# general_Interface.net
KiCad netlist of a schematic drawn in Altium Designer
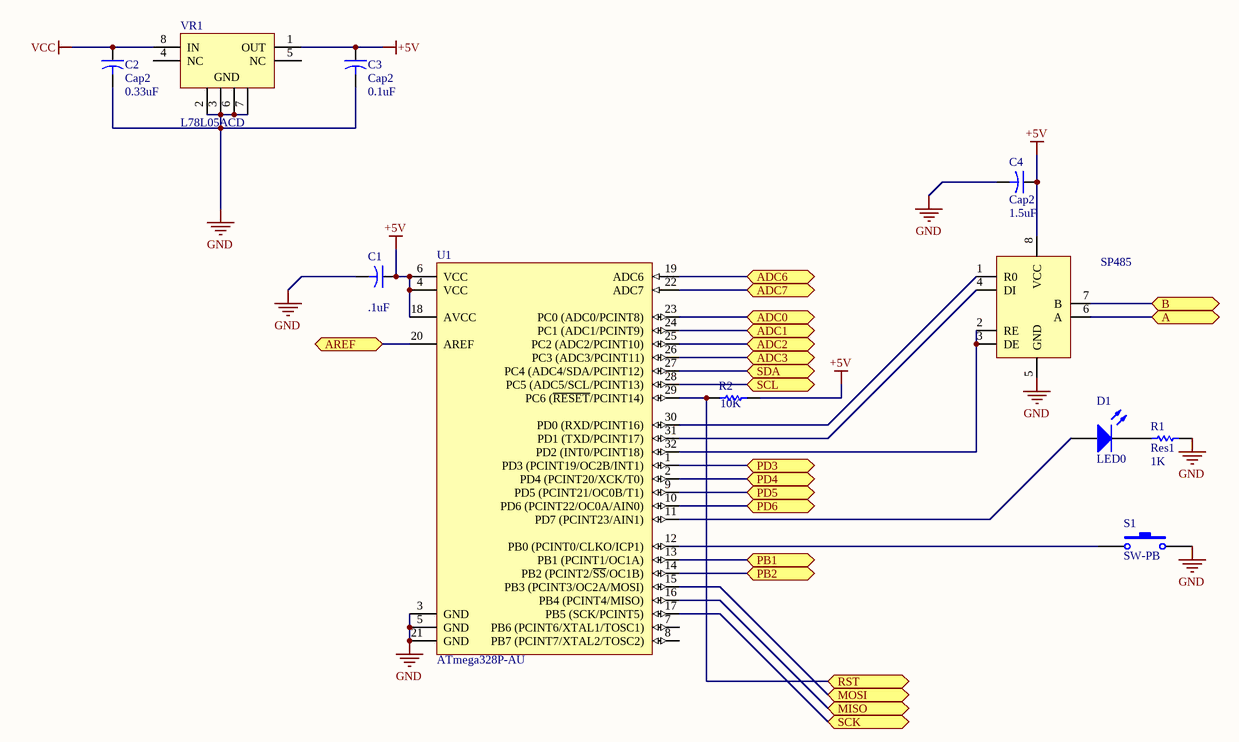
[diagram p0: general_Interface.SchDoc]

(export (version "E")
  (design (tool "Eeschema 10.0.6"))
  (components
    (comp (ref "C1")
      (value ".1uF")
      (footprint "6-0805_M")
      (description "Capacitor")
      (fields (field (name "PUBLISHER") "Altium Limited"))
      (libsource (lib "Miscellaneous Devices") (part "Cap2"))
    )
    (comp (ref "C2")
      (value "Cap2")
      (footprint "6-0805_M")
      (description "Capacitor")
      (fields (field (name "ALTIUM_VALUE") "0.33uF") (field (name "PUBLISHER") "Altium Limited"))
      (libsource (lib "Miscellaneous Devices") (part "Cap2"))
    )
    (comp (ref "C3")
      (value "Cap2")
      (footprint "6-0805_M")
      (description "Capacitor")
      (fields (field (name "ALTIUM_VALUE") "0.1uF") (field (name "PUBLISHER") "Altium Limited"))
      (libsource (lib "Miscellaneous Devices") (part "Cap2"))
    )
    (comp (ref "C4")
      (value "Cap2")
      (footprint "6-0805_M")
      (description "Capacitor")
      (fields (field (name "ALTIUM_VALUE") "1.5uF") (field (name "PUBLISHER") "Altium Limited"))
      (libsource (lib "Miscellaneous Devices") (part "Cap2"))
    )
    (comp (ref "D1")
      (value "LED0")
      (footprint "1608[0603]")
      (description "Typical INFRARED GaAs LED")
      (fields (field (name "PUBLISHER") "Altium Limited"))
      (libsource (lib "Miscellaneous Devices") (part "LED0"))
    )
    (comp (ref "R1")
      (value "Res1")
      (footprint "0603")
      (description "Resistor")
      (fields (field (name "ALTIUM_VALUE") "1K") (field (name "PUBLISHER") "Altium Limited"))
      (libsource (lib "Miscellaneous Devices") (part "Res1"))
    )
    (comp (ref "R2")
      (value "10K")
      (footprint "0603")
      (description "Resistor")
      (fields (field (name "PUBLISHER") "Altium Limited"))
      (libsource (lib "Miscellaneous Devices") (part "Res1"))
    )
    (comp (ref "S1")
      (value "SW-PB")
      (footprint "ADTSM3")
      (description "Switch")
      (fields (field (name "PUBLISHER") "Altium Limited"))
      (libsource (lib "Miscellaneous Devices") (part "SW-PB"))
    )
    (comp (ref "SP485")
      (value "SP485")
      (footprint "SO8_M")
      (description "SN75176")
      (libsource (lib "MABSS") (part "SP485"))
    )
    (comp (ref "U1")
      (value "ATmega328P-AU")
      (footprint "32A_M")
      (libsource (lib "Atmel Microcontroller megaAVR") (part "ATmega328P-AU"))
    )
    (comp (ref "VR1")
      (value "L78L05ACD")
      (footprint "SO8_N")
      (description "Positive Voltage Regulator")
      (fields (field (name "PUBLISHER") "Altium Limited"))
      (libsource (lib "ST Power Mgt Voltage Regulator") (part "L78L05ACD"))
    )
  )
  (nets
    (net (code "1") (name "+5V") (class "Default")
      (node (ref "C1") (pin "1") (pinfunction "1_1") (pintype "passive"))
      (node (ref "C3") (pin "1") (pinfunction "1_1") (pintype "passive"))
      (node (ref "C4") (pin "1") (pinfunction "1_1") (pintype "passive"))
      (node (ref "R2") (pin "2") (pinfunction "2_2") (pintype "passive"))
      (node (ref "SP485") (pin "8") (pinfunction "VCC_8") (pintype "passive"))
      (node (ref "U1") (pin "18") (pinfunction "AVCC_18") (pintype "power_in"))
      (node (ref "U1") (pin "4") (pinfunction "VCC_4") (pintype "power_in"))
      (node (ref "U1") (pin "6") (pinfunction "VCC_6") (pintype "power_in"))
      (node (ref "VR1") (pin "1") (pinfunction "OUT_1") (pintype "power_in"))
    )
    (net (code "2") (name "/A") (class "Default")
      (node (ref "SP485") (pin "6") (pinfunction "A_6") (pintype "passive"))
    )
    (net (code "3") (name "/ADC0") (class "Default")
      (node (ref "U1") (pin "23") (pinfunction "PC0_(ADC0/PCINT8)_23") (pintype "bidirectional"))
    )
    (net (code "4") (name "/ADC1") (class "Default")
      (node (ref "U1") (pin "24") (pinfunction "PC1_(ADC1/PCINT9)_24") (pintype "bidirectional"))
    )
    (net (code "5") (name "/ADC2") (class "Default")
      (node (ref "U1") (pin "25") (pinfunction "PC2_(ADC2/PCINT10)_25") (pintype "bidirectional"))
    )
    (net (code "6") (name "/ADC3") (class "Default")
      (node (ref "U1") (pin "26") (pinfunction "PC3_(ADC3/PCINT11)_26") (pintype "bidirectional"))
    )
    (net (code "7") (name "/ADC6") (class "Default")
      (node (ref "U1") (pin "19") (pinfunction "ADC6_19") (pintype "input"))
    )
    (net (code "8") (name "/ADC7") (class "Default")
      (node (ref "U1") (pin "22") (pinfunction "ADC7_22") (pintype "input"))
    )
    (net (code "9") (name "/AREF") (class "Default")
      (node (ref "U1") (pin "20") (pinfunction "AREF_20") (pintype "passive"))
    )
    (net (code "10") (name "/B") (class "Default")
      (node (ref "SP485") (pin "7") (pinfunction "B_7") (pintype "passive"))
    )
    (net (code "11") (name "/MISO") (class "Default")
      (node (ref "U1") (pin "16") (pinfunction "PB4_(PCINT4/MISO)_16") (pintype "bidirectional"))
    )
    (net (code "12") (name "/MOSI") (class "Default")
      (node (ref "U1") (pin "15") (pinfunction "PB3_(PCINT3/OC2A/MOSI)_15") (pintype "bidirectional"))
    )
    (net (code "13") (name "/PB1") (class "Default")
      (node (ref "U1") (pin "13") (pinfunction "PB1_(PCINT1/OC1A)_13") (pintype "bidirectional"))
    )
    (net (code "14") (name "/PB2") (class "Default")
      (node (ref "U1") (pin "14") (pinfunction "PB2_(PCINT2/~{SS}/OC1B)_14") (pintype "bidirectional"))
    )
    (net (code "15") (name "/PD3") (class "Default")
      (node (ref "U1") (pin "1") (pinfunction "PD3_(PCINT19/OC2B/INT1)_1") (pintype "bidirectional"))
    )
    (net (code "16") (name "/PD4") (class "Default")
      (node (ref "U1") (pin "2") (pinfunction "PD4_(PCINT20/XCK/T0)_2") (pintype "bidirectional"))
    )
    (net (code "17") (name "/PD5") (class "Default")
      (node (ref "U1") (pin "9") (pinfunction "PD5_(PCINT21/OC0B/T1)_9") (pintype "bidirectional"))
    )
    (net (code "18") (name "/PD6") (class "Default")
      (node (ref "U1") (pin "10") (pinfunction "PD6_(PCINT22/OC0A/AIN0)_10") (pintype "bidirectional"))
    )
    (net (code "19") (name "/RST") (class "Default")
      (node (ref "R2") (pin "1") (pinfunction "1_1") (pintype "passive"))
      (node (ref "U1") (pin "29") (pinfunction "PC6_(~{RESET}/PCINT14)_29") (pintype "bidirectional"))
    )
    (net (code "20") (name "/SCK") (class "Default")
      (node (ref "U1") (pin "17") (pinfunction "PB5_(SCK/PCINT5)_17") (pintype "bidirectional"))
    )
    (net (code "21") (name "/SCL") (class "Default")
      (node (ref "U1") (pin "28") (pinfunction "PC5_(ADC5/SCL/PCINT13)_28") (pintype "bidirectional"))
    )
    (net (code "22") (name "/SDA") (class "Default")
      (node (ref "U1") (pin "27") (pinfunction "PC4_(ADC4/SDA/PCINT12)_27") (pintype "bidirectional"))
    )
    (net (code "23") (name "GND") (class "Default")
      (node (ref "C1") (pin "2") (pinfunction "2_2") (pintype "passive"))
      (node (ref "C2") (pin "2") (pinfunction "2_2") (pintype "passive"))
      (node (ref "C3") (pin "2") (pinfunction "2_2") (pintype "passive"))
      (node (ref "C4") (pin "2") (pinfunction "2_2") (pintype "passive"))
      (node (ref "R1") (pin "2") (pinfunction "2_2") (pintype "passive"))
      (node (ref "S1") (pin "2") (pinfunction "2_2") (pintype "passive"))
      (node (ref "SP485") (pin "5") (pinfunction "GND_5") (pintype "passive"))
      (node (ref "U1") (pin "21") (pinfunction "GND_21") (pintype "power_in"))
      (node (ref "U1") (pin "3") (pinfunction "GND_3") (pintype "power_in"))
      (node (ref "U1") (pin "5") (pinfunction "GND_5") (pintype "power_in"))
      (node (ref "VR1") (pin "2") (pinfunction "GND_2") (pintype "power_in"))
      (node (ref "VR1") (pin "3") (pinfunction "GND_3") (pintype "power_in"))
      (node (ref "VR1") (pin "6") (pinfunction "GND_6") (pintype "power_in"))
      (node (ref "VR1") (pin "7") (pinfunction "GND_7") (pintype "power_in"))
    )
    (net (code "24") (name "Net-(D1-A)") (class "Default")
      (node (ref "D1") (pin "1") (pinfunction "A_1") (pintype "passive"))
      (node (ref "U1") (pin "11") (pinfunction "PD7_(PCINT23/AIN1)_11") (pintype "bidirectional"))
    )
    (net (code "25") (name "Net-(D1-K)") (class "Default")
      (node (ref "D1") (pin "2") (pinfunction "K_2") (pintype "passive"))
      (node (ref "R1") (pin "1") (pinfunction "1_1") (pintype "passive"))
    )
    (net (code "26") (name "Net-(SP485-DE)") (class "Default")
      (node (ref "SP485") (pin "2") (pinfunction "RE_2") (pintype "passive"))
      (node (ref "SP485") (pin "3") (pinfunction "DE_3") (pintype "passive"))
      (node (ref "U1") (pin "32") (pinfunction "PD2_(INT0/PCINT18)_32") (pintype "bidirectional"))
    )
    (net (code "27") (name "Net-(SP485-DI)") (class "Default")
      (node (ref "SP485") (pin "4") (pinfunction "DI_4") (pintype "passive"))
      (node (ref "U1") (pin "31") (pinfunction "PD1_(TXD/PCINT17)_31") (pintype "bidirectional"))
    )
    (net (code "28") (name "Net-(SP485-R0)") (class "Default")
      (node (ref "SP485") (pin "1") (pinfunction "R0_1") (pintype "passive"))
      (node (ref "U1") (pin "30") (pinfunction "PD0_(RXD/PCINT16)_30") (pintype "bidirectional"))
    )
    (net (code "29") (name "Net-(U1-PB0_(PCINT0{slash}CLKO{slash}ICP1))") (class "Default")
      (node (ref "S1") (pin "1") (pinfunction "1_1") (pintype "passive"))
      (node (ref "U1") (pin "12") (pinfunction "PB0_(PCINT0/CLKO/ICP1)_12") (pintype "bidirectional"))
    )
    (net (code "30") (name "VCC") (class "Default")
      (node (ref "C2") (pin "1") (pinfunction "1_1") (pintype "passive"))
      (node (ref "VR1") (pin "8") (pinfunction "IN_8") (pintype "power_in"))
    )
    (net (code "31") (name "unconnected-(U1-PB6_(PCINT6{slash}XTAL1{slash}TOSC1)-Pad7)") (class "Default")
      (node (ref "U1") (pin "7") (pinfunction "PB6_(PCINT6/XTAL1/TOSC1)_7") (pintype "bidirectional"))
    )
    (net (code "32") (name "unconnected-(U1-PB7_(PCINT7{slash}XTAL2{slash}TOSC2)-Pad8)") (class "Default")
      (node (ref "U1") (pin "8") (pinfunction "PB7_(PCINT7/XTAL2/TOSC2)_8") (pintype "bidirectional"))
    )
    (net (code "33") (name "unconnected-(VR1-NC-Pad4)") (class "Default")
      (node (ref "VR1") (pin "4") (pinfunction "NC_4") (pintype "passive"))
    )
    (net (code "34") (name "unconnected-(VR1-NC-Pad5)") (class "Default")
      (node (ref "VR1") (pin "5") (pinfunction "NC_5") (pintype "passive"))
    )
  )
)
